# kkClave.net
KiCad netlist of a schematic drawn in EAGLE
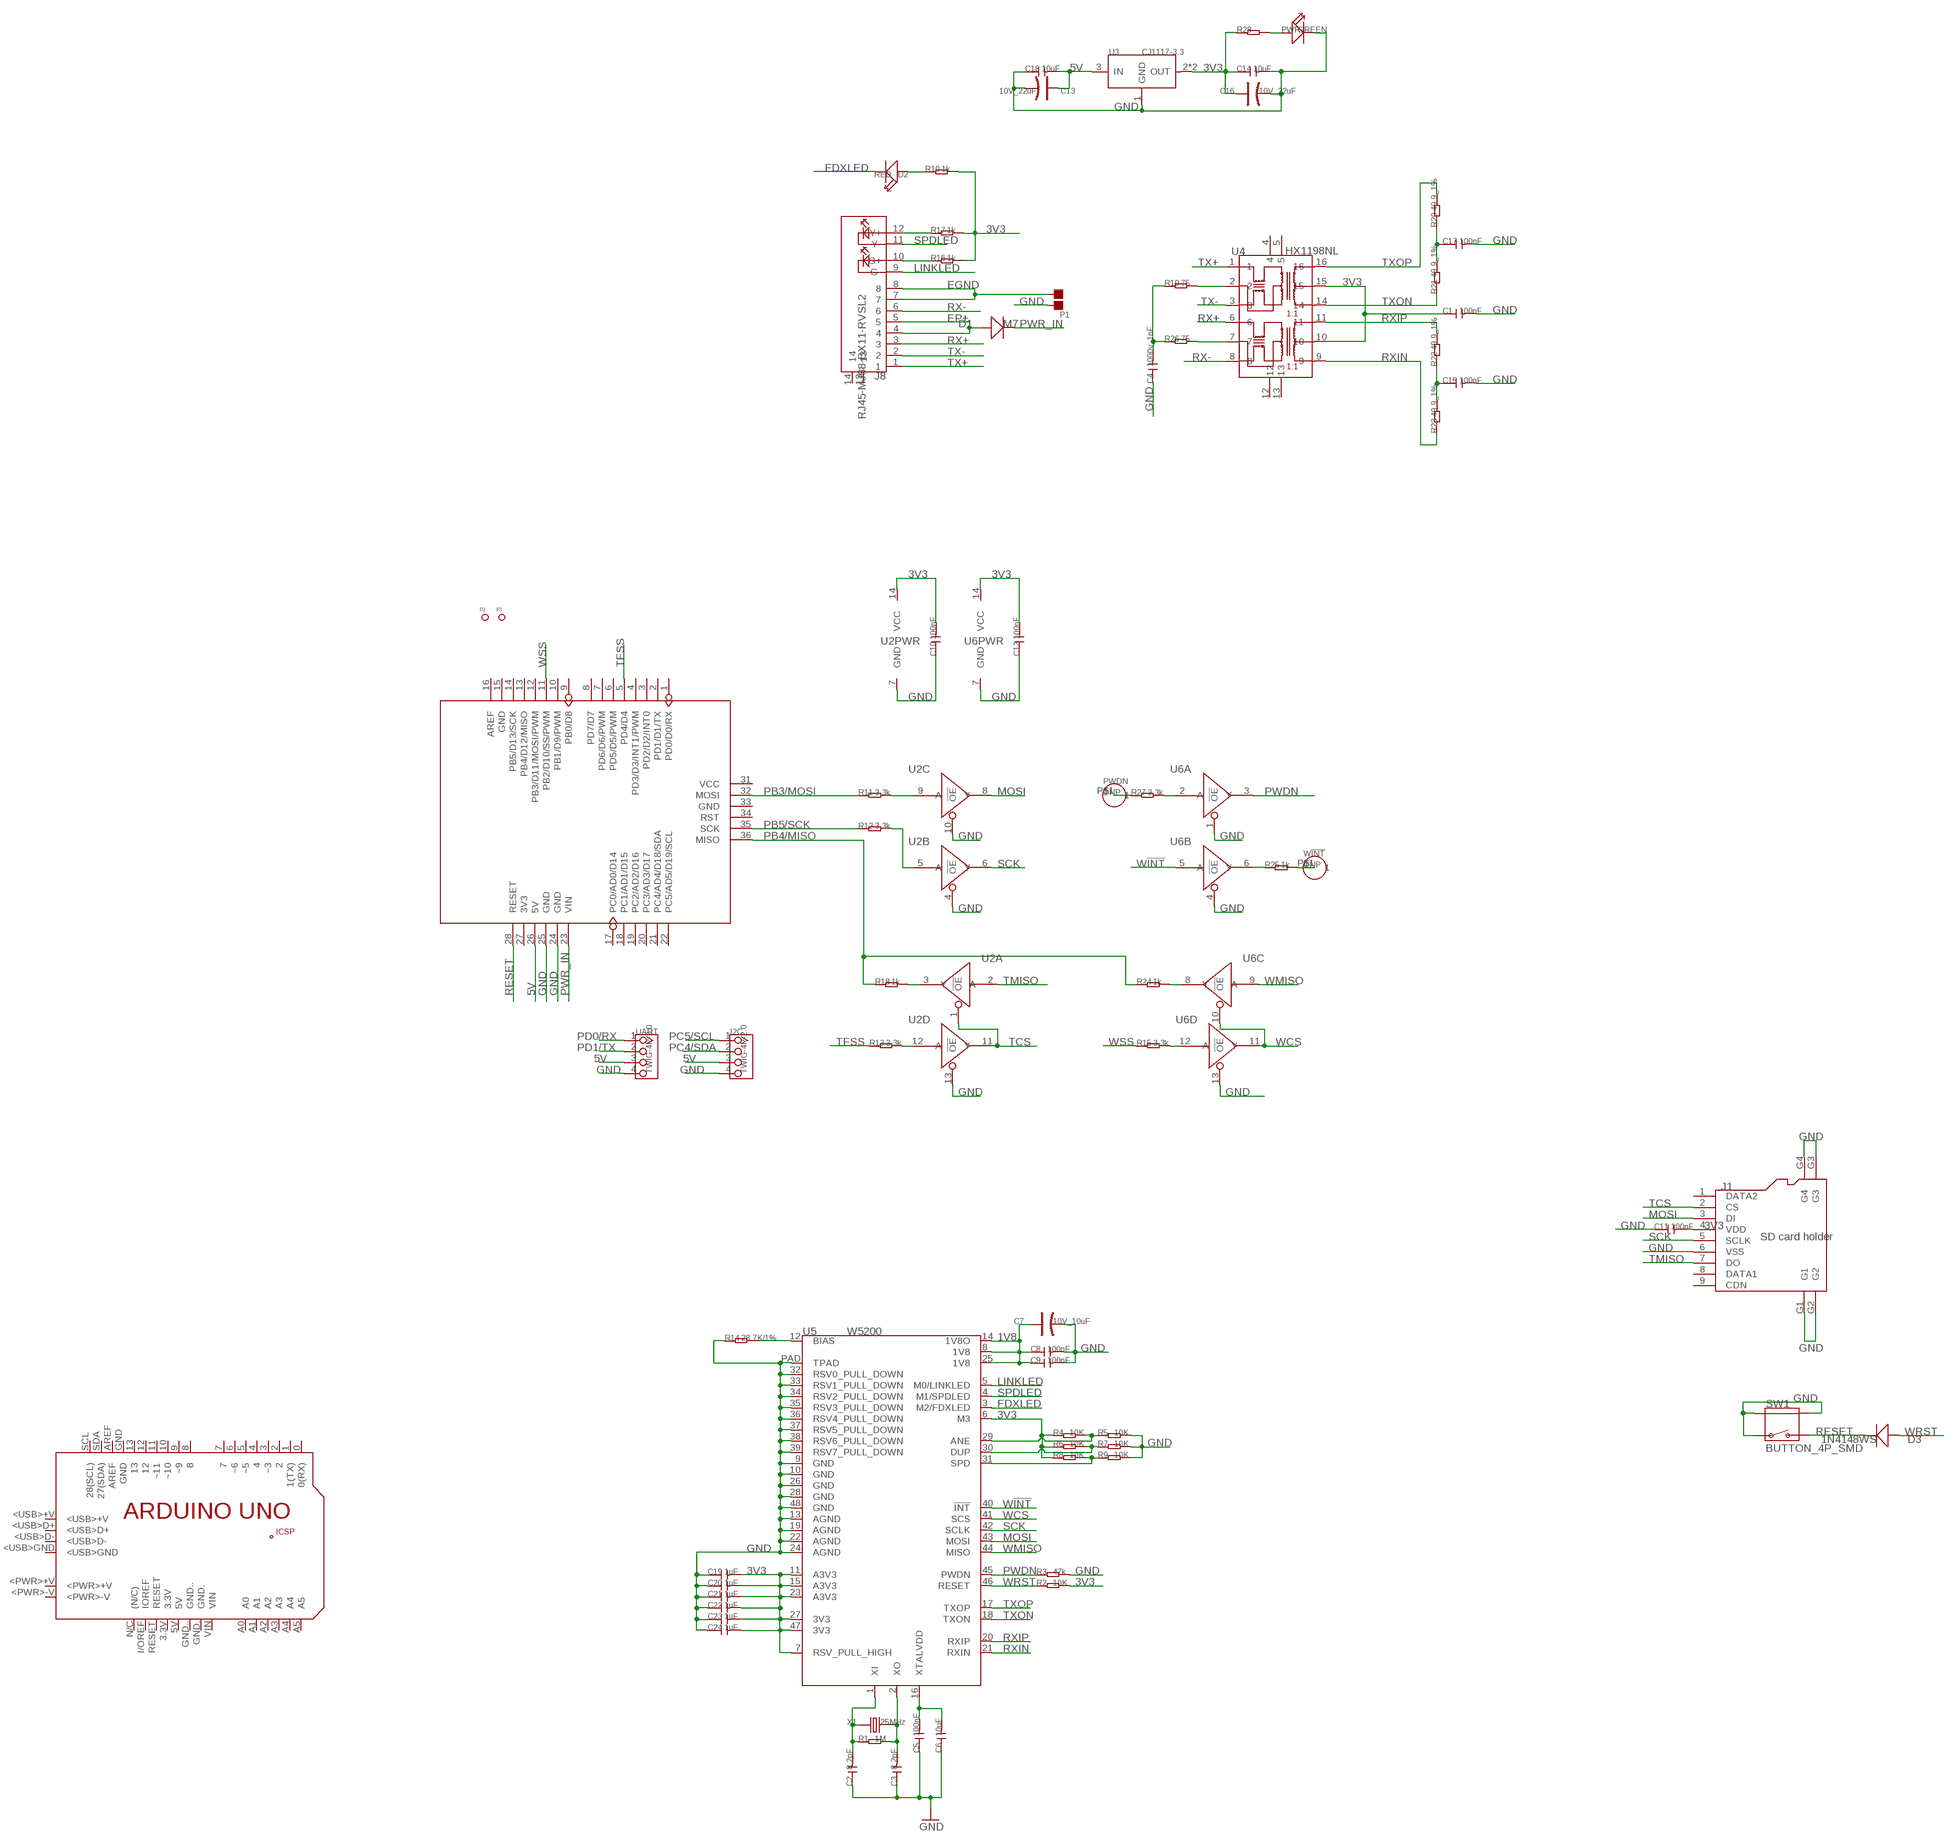
[diagram p0: schematic, sheet 1]

(export (version "E")
  (design (tool "Eeschema 10.0.6"))
  (components
    (comp (ref "C1")
      (value "100nF")
      (footprint "eagle-import:C0603")
      (libsource (lib "eagle-import") (part "C-0603"))
    )
    (comp (ref "C2")
      (value "8.2pF")
      (footprint "eagle-import:C0603")
      (libsource (lib "eagle-import") (part "C-0603"))
    )
    (comp (ref "C3")
      (value "8.2pF")
      (footprint "eagle-import:C0603")
      (libsource (lib "eagle-import") (part "C-0603"))
    )
    (comp (ref "C4")
      (value "1000v_1nF")
      (footprint "eagle-import:C1206")
      (libsource (lib "eagle-import") (part "C-1206"))
    )
    (comp (ref "C5")
      (value "100nF")
      (footprint "eagle-import:C0603")
      (libsource (lib "eagle-import") (part "C-0603"))
    )
    (comp (ref "C6")
      (value "10uF")
      (footprint "eagle-import:C0805")
      (libsource (lib "eagle-import") (part "C-0805"))
    )
    (comp (ref "C7")
      (value "10V_10uF")
      (footprint "eagle-import:AVX-A")
      (libsource (lib "eagle-import") (part "CAP-AVX-A"))
    )
    (comp (ref "C8")
      (value "100nF")
      (footprint "eagle-import:C0603")
      (libsource (lib "eagle-import") (part "C-0603"))
    )
    (comp (ref "C9")
      (value "100nF")
      (footprint "eagle-import:C0603")
      (libsource (lib "eagle-import") (part "C-0603"))
    )
    (comp (ref "C10")
      (value "100nF")
      (footprint "eagle-import:C0603")
      (libsource (lib "eagle-import") (part "C-0603"))
    )
    (comp (ref "C11")
      (value "100nF")
      (footprint "eagle-import:C0603")
      (libsource (lib "eagle-import") (part "C-0603"))
    )
    (comp (ref "C12")
      (value "100nF")
      (footprint "eagle-import:C0603")
      (libsource (lib "eagle-import") (part "C-0603"))
    )
    (comp (ref "C13")
      (value "10V_22uF")
      (footprint "eagle-import:AVX-B")
      (libsource (lib "eagle-import") (part "CAP-AVX-B"))
    )
    (comp (ref "C14")
      (value "10uF")
      (footprint "eagle-import:C0805")
      (libsource (lib "eagle-import") (part "C-0805"))
    )
    (comp (ref "C15")
      (value "100nF")
      (footprint "eagle-import:C0603")
      (libsource (lib "eagle-import") (part "C-0603"))
    )
    (comp (ref "C16")
      (value "10V_22uF")
      (footprint "eagle-import:AVX-B")
      (libsource (lib "eagle-import") (part "CAP-AVX-B"))
    )
    (comp (ref "C17")
      (value "100nF")
      (footprint "eagle-import:C0603")
      (libsource (lib "eagle-import") (part "C-0603"))
    )
    (comp (ref "C18")
      (value "10uF")
      (footprint "eagle-import:C0805")
      (libsource (lib "eagle-import") (part "C-0805"))
    )
    (comp (ref "C19")
      (value "1uF")
      (footprint "eagle-import:C0805")
      (libsource (lib "eagle-import") (part "C-0805"))
    )
    (comp (ref "C20")
      (value "1uF")
      (footprint "eagle-import:C0805")
      (libsource (lib "eagle-import") (part "C-0805"))
    )
    (comp (ref "C21")
      (value "1uF")
      (footprint "eagle-import:C0805")
      (libsource (lib "eagle-import") (part "C-0805"))
    )
    (comp (ref "C22")
      (value "1uF")
      (footprint "eagle-import:C0805")
      (libsource (lib "eagle-import") (part "C-0805"))
    )
    (comp (ref "C23")
      (value "1uF")
      (footprint "eagle-import:C0805")
      (libsource (lib "eagle-import") (part "C-0805"))
    )
    (comp (ref "C24")
      (value "1uF")
      (footprint "eagle-import:C0805")
      (libsource (lib "eagle-import") (part "C-0805"))
    )
    (comp (ref "D1")
      (value "M7")
      (footprint "eagle-import:D2010")
      (libsource (lib "eagle-import") (part "D'SMA'"))
    )
    (comp (ref "D2")
      (value "RED")
      (footprint "eagle-import:LED-0603")
      (libsource (lib "eagle-import") (part "LED'0603'"))
    )
    (comp (ref "D3")
      (value "1N4148WS")
      (footprint "eagle-import:SOD323")
      (libsource (lib "eagle-import") (part "D'0805'"))
    )
    (comp (ref "I2C")
      (value "TWIG-4P-2.0")
      (footprint "eagle-import:4P-2.0")
      (libsource (lib "eagle-import") (part "TWIG-4P-2.0-2.0"))
    )
    (comp (ref "J1")
      (value "SD card holder")
      (footprint "eagle-import:9P-SMD-W_-RING")
      (libsource (lib "eagle-import") (part "HOLDER-MICROSD-9P"))
    )
    (comp (ref "J8")
      (value "RJ45-MJ88-BX11-RVSL2")
      (footprint "eagle-import:RJ45-MJ88-BX11-RVSL2")
      (libsource (lib "eagle-import") (part "RJ45-MJ88-BX11-RVSL2"))
    )
    (comp (ref "P1")
      (value "DNP")
      (footprint "eagle-import:2P-SMD-1.78X1.27")
      (libsource (lib "eagle-import") (part "PAD-JUMPER-2P"))
    )
    (comp (ref "P2")
      (value "PAD-MARK")
      (footprint "eagle-import:ROUND-MARK-1.0")
      (fields (field (name "PARTNO") "DNP"))
      (libsource (lib "eagle-import") (part "PAD-MARK"))
    )
    (comp (ref "P3")
      (value "PAD-MARK")
      (footprint "eagle-import:ROUND-MARK-1.0")
      (fields (field (name "PARTNO") "DNP"))
      (libsource (lib "eagle-import") (part "PAD-MARK"))
    )
    (comp (ref "PCB1")
      (value "ARDUINO_UNO")
      (footprint "eagle-import:ARDUINO_UNO")
      (libsource (lib "eagle-import") (part "ARDUINO_UNO"))
    )
    (comp (ref "PWDN")
      (value "DNP")
      (footprint "eagle-import:1P-65_35MIL")
      (libsource (lib "eagle-import") (part "HEADER-1P-35"))
    )
    (comp (ref "PWR")
      (value "GREEN")
      (footprint "eagle-import:LED-0603")
      (libsource (lib "eagle-import") (part "LED'0603'"))
    )
    (comp (ref "R1")
      (value "1M")
      (footprint "eagle-import:R0603")
      (libsource (lib "eagle-import") (part "R-0603"))
    )
    (comp (ref "R2")
      (value "10K")
      (footprint "eagle-import:R0603")
      (libsource (lib "eagle-import") (part "R-0603"))
    )
    (comp (ref "R3")
      (value "47k")
      (footprint "eagle-import:R0603")
      (libsource (lib "eagle-import") (part "R-0603"))
    )
    (comp (ref "R4")
      (value "10K")
      (footprint "eagle-import:R0603")
      (libsource (lib "eagle-import") (part "R-0603"))
    )
    (comp (ref "R5")
      (value "10K")
      (footprint "eagle-import:R0603")
      (libsource (lib "eagle-import") (part "R-0603"))
    )
    (comp (ref "R6")
      (value "10K")
      (footprint "eagle-import:R0603")
      (libsource (lib "eagle-import") (part "R-0603"))
    )
    (comp (ref "R7")
      (value "10K")
      (footprint "eagle-import:R0603")
      (libsource (lib "eagle-import") (part "R-0603"))
    )
    (comp (ref "R8")
      (value "10K")
      (footprint "eagle-import:R0603")
      (libsource (lib "eagle-import") (part "R-0603"))
    )
    (comp (ref "R9")
      (value "10K")
      (footprint "eagle-import:R0603")
      (libsource (lib "eagle-import") (part "R-0603"))
    )
    (comp (ref "R10")
      (value "1k")
      (footprint "eagle-import:R0603")
      (libsource (lib "eagle-import") (part "R-0603"))
    )
    (comp (ref "R11")
      (value "3.3k")
      (footprint "eagle-import:R0603")
      (libsource (lib "eagle-import") (part "R-0603"))
    )
    (comp (ref "R12")
      (value "3.3k")
      (footprint "eagle-import:R0603")
      (libsource (lib "eagle-import") (part "R-0603"))
    )
    (comp (ref "R13")
      (value "3.3k")
      (footprint "eagle-import:R0603")
      (libsource (lib "eagle-import") (part "R-0603"))
    )
    (comp (ref "R14")
      (value "28.7K/1%")
      (footprint "eagle-import:R0603")
      (libsource (lib "eagle-import") (part "R-0603"))
    )
    (comp (ref "R15")
      (value "3.3k")
      (footprint "eagle-import:R0603")
      (libsource (lib "eagle-import") (part "R-0603"))
    )
    (comp (ref "R16")
      (value "1k")
      (footprint "eagle-import:R0603")
      (libsource (lib "eagle-import") (part "R-0603"))
    )
    (comp (ref "R17")
      (value "1k")
      (footprint "eagle-import:R0603")
      (libsource (lib "eagle-import") (part "R-0603"))
    )
    (comp (ref "R18")
      (value "1k")
      (footprint "eagle-import:R0603")
      (libsource (lib "eagle-import") (part "R-0603"))
    )
    (comp (ref "R19")
      (value "75")
      (footprint "eagle-import:R0603")
      (libsource (lib "eagle-import") (part "R-0603"))
    )
    (comp (ref "R20")
      (value "49.9_1%")
      (footprint "eagle-import:R0603")
      (libsource (lib "eagle-import") (part "R-0603"))
    )
    (comp (ref "R21")
      (value "49.9_1%")
      (footprint "eagle-import:R0603")
      (libsource (lib "eagle-import") (part "R-0603"))
    )
    (comp (ref "R22")
      (value "49.9_1%")
      (footprint "eagle-import:R0603")
      (libsource (lib "eagle-import") (part "R-0603"))
    )
    (comp (ref "R23")
      (value "49.9_1%")
      (footprint "eagle-import:R0603")
      (libsource (lib "eagle-import") (part "R-0603"))
    )
    (comp (ref "R24")
      (value "1k")
      (footprint "eagle-import:R0603")
      (libsource (lib "eagle-import") (part "R-0603"))
    )
    (comp (ref "R25")
      (value "1k")
      (footprint "eagle-import:R0603")
      (libsource (lib "eagle-import") (part "R-0603"))
    )
    (comp (ref "R26")
      (value "75")
      (footprint "eagle-import:R0603")
      (libsource (lib "eagle-import") (part "R-0603"))
    )
    (comp (ref "R27")
      (value "3.3k")
      (footprint "eagle-import:R0603")
      (libsource (lib "eagle-import") (part "R-0603"))
    )
    (comp (ref "R28")
      (value "R-0603")
      (footprint "eagle-import:R0603")
      (libsource (lib "eagle-import") (part "R-0603"))
    )
    (comp (ref "SW1")
      (value "BUTTON_4P_SMD")
      (footprint "eagle-import:4P-SMD-7X3.5X3.5")
      (libsource (lib "eagle-import") (part "BUTTON_4P_SMD"))
    )
    (comp (ref "U1")
      (value "ARDUINO")
      (footprint "eagle-import:ARDUINO")
      (libsource (lib "eagle-import") (part "ARDUINO"))
    )
    (comp (ref "U2")
      (value "74VHC125PW")
      (footprint "eagle-import:TSSOP14")
      (libsource (lib "eagle-import") (part "74V125PWHC"))
    )
    (comp (ref "U3")
      (value "CJ1117-3.3")
      (footprint "eagle-import:SOT-223")
      (libsource (lib "eagle-import") (part "LD1117S"))
    )
    (comp (ref "U4")
      (value "HX1198NL")
      (footprint "eagle-import:SOIC16-9.53")
      (libsource (lib "eagle-import") (part "HX1198NL"))
    )
    (comp (ref "U5")
      (value "W5200")
      (footprint "eagle-import:QFN48")
      (libsource (lib "eagle-import") (part "W5200"))
    )
    (comp (ref "U6")
      (value "74VHC125PW")
      (footprint "eagle-import:TSSOP14")
      (libsource (lib "eagle-import") (part "74V125PWHC"))
    )
    (comp (ref "UART")
      (value "TWIG-4P-2.0")
      (footprint "eagle-import:4P-2.0")
      (libsource (lib "eagle-import") (part "TWIG-4P-2.0-2.0"))
    )
    (comp (ref "W!INT")
      (value "DNP")
      (footprint "eagle-import:1P-65_35MIL")
      (libsource (lib "eagle-import") (part "HEADER-1P-35"))
    )
    (comp (ref "X1")
      (value "25MHz")
      (footprint "eagle-import:2P-SMD-5X3.2")
      (libsource (lib "eagle-import") (part "CRYSTAL'5032'"))
    )
  )
  (nets
    (net (code "1") (name "/1V8") (class "Default")
      (node (ref "C7") (pin "+") (pinfunction "+_+") (pintype "passive"))
      (node (ref "C8") (pin "1") (pinfunction "1_1") (pintype "passive"))
      (node (ref "C9") (pin "1") (pinfunction "1_1") (pintype "passive"))
      (node (ref "U5") (pin "14") (pinfunction "1V8O_14") (pintype "bidirectional"))
      (node (ref "U5") (pin "25") (pinfunction "1V8_25") (pintype "bidirectional"))
      (node (ref "U5") (pin "8") (pinfunction "1V8_8") (pintype "bidirectional"))
    )
    (net (code "2") (name "/3V3") (class "Default")
      (node (ref "C1") (pin "1") (pinfunction "1_1") (pintype "passive"))
      (node (ref "C10") (pin "2") (pinfunction "2_2") (pintype "passive"))
      (node (ref "C11") (pin "2") (pinfunction "2_2") (pintype "passive"))
      (node (ref "C12") (pin "2") (pinfunction "2_2") (pintype "passive"))
      (node (ref "C14") (pin "1") (pinfunction "1_1") (pintype "passive"))
      (node (ref "C16") (pin "+") (pinfunction "+_+") (pintype "passive"))
      (node (ref "C19") (pin "2") (pinfunction "2_2") (pintype "passive"))
      (node (ref "C20") (pin "2") (pinfunction "2_2") (pintype "passive"))
      (node (ref "C21") (pin "2") (pinfunction "2_2") (pintype "passive"))
      (node (ref "C22") (pin "2") (pinfunction "2_2") (pintype "passive"))
      (node (ref "C23") (pin "2") (pinfunction "2_2") (pintype "passive"))
      (node (ref "C24") (pin "2") (pinfunction "2_2") (pintype "passive"))
      (node (ref "J1") (pin "4") (pinfunction "VDD_4") (pintype "bidirectional"))
      (node (ref "R10") (pin "2") (pinfunction "2_2") (pintype "passive"))
      (node (ref "R16") (pin "2") (pinfunction "2_2") (pintype "passive"))
      (node (ref "R17") (pin "2") (pinfunction "2_2") (pintype "passive"))
      (node (ref "R2") (pin "2") (pinfunction "2_2") (pintype "passive"))
      (node (ref "R28") (pin "1") (pinfunction "1_1") (pintype "passive"))
      (node (ref "R4") (pin "1") (pinfunction "1_1") (pintype "passive"))
      (node (ref "R6") (pin "1") (pinfunction "1_1") (pintype "passive"))
      (node (ref "R8") (pin "1") (pinfunction "1_1") (pintype "passive"))
      (node (ref "U2") (pin "14") (pinfunction "VCC_14") (pintype "power_in"))
      (node (ref "U3") (pin "2") (pinfunction "OUT_2") (pintype "bidirectional"))
      (node (ref "U3") (pin "TER") (pinfunction "OUT_TER") (pintype "bidirectional"))
      (node (ref "U4") (pin "10") (pinfunction "10_10") (pintype "bidirectional"))
      (node (ref "U4") (pin "15") (pinfunction "15_15") (pintype "bidirectional"))
      (node (ref "U5") (pin "11") (pinfunction "A3V3_11") (pintype "bidirectional"))
      (node (ref "U5") (pin "15") (pinfunction "A3V3_15") (pintype "bidirectional"))
      (node (ref "U5") (pin "23") (pinfunction "A3V3_23") (pintype "bidirectional"))
      (node (ref "U5") (pin "27") (pinfunction "3V3_27") (pintype "bidirectional"))
      (node (ref "U5") (pin "47") (pinfunction "3V3_47") (pintype "bidirectional"))
      (node (ref "U5") (pin "6") (pinfunction "M3_6") (pintype "bidirectional"))
      (node (ref "U5") (pin "7") (pinfunction "RSV_PULL_HIGH_7") (pintype "bidirectional"))
      (node (ref "U6") (pin "14") (pinfunction "VCC_14") (pintype "power_in"))
    )
    (net (code "3") (name "/5V") (class "Default")
      (node (ref "C13") (pin "+") (pinfunction "+_+") (pintype "passive"))
      (node (ref "C18") (pin "2") (pinfunction "2_2") (pintype "passive"))
      (node (ref "I2C") (pin "3") (pinfunction "3_3") (pintype "bidirectional"))
      (node (ref "U1") (pin "26") (pinfunction "5V_26") (pintype "bidirectional"))
      (node (ref "U3") (pin "3") (pinfunction "IN_3") (pintype "bidirectional"))
      (node (ref "UART") (pin "3") (pinfunction "3_3") (pintype "bidirectional"))
    )
    (net (code "4") (name "/EGND") (class "Default")
      (node (ref "J8") (pin "7") (pinfunction "7_7") (pintype "bidirectional"))
      (node (ref "J8") (pin "8") (pinfunction "8_8") (pintype "bidirectional"))
      (node (ref "P1") (pin "1") (pinfunction "1_1") (pintype "bidirectional"))
    )
    (net (code "5") (name "/EP+") (class "Default")
      (node (ref "D1") (pin "+") (pinfunction "+_+") (pintype "passive"))
      (node (ref "J8") (pin "4") (pinfunction "4_4") (pintype "bidirectional"))
      (node (ref "J8") (pin "5") (pinfunction "5_5") (pintype "bidirectional"))
    )
    (net (code "6") (name "/FDXLED") (class "Default")
      (node (ref "D2") (pin "-") (pinfunction "-_-") (pintype "passive"))
      (node (ref "U5") (pin "3") (pinfunction "M2/FDXLED_3") (pintype "bidirectional"))
    )
    (net (code "7") (name "/LINKLED") (class "Default")
      (node (ref "J8") (pin "9") (pinfunction "G-_9") (pintype "bidirectional"))
      (node (ref "U5") (pin "5") (pinfunction "M0/LINKLED_5") (pintype "bidirectional"))
    )
    (net (code "8") (name "/MOSI") (class "Default")
      (node (ref "J1") (pin "3") (pinfunction "DI_3") (pintype "bidirectional"))
      (node (ref "U2") (pin "8") (pinfunction "Y_8") (pintype "bidirectional"))
      (node (ref "U5") (pin "43") (pinfunction "MOSI_43") (pintype "bidirectional"))
    )
    (net (code "9") (name "/PB3{slash}MOSI") (class "Default")
      (node (ref "R11") (pin "1") (pinfunction "1_1") (pintype "passive"))
      (node (ref "U1") (pin "32") (pinfunction "MOSI_32") (pintype "bidirectional"))
    )
    (net (code "10") (name "/PB4{slash}MISO") (class "Default")
      (node (ref "R18") (pin "1") (pinfunction "1_1") (pintype "passive"))
      (node (ref "R24") (pin "1") (pinfunction "1_1") (pintype "passive"))
      (node (ref "U1") (pin "36") (pinfunction "MISO_36") (pintype "bidirectional"))
    )
    (net (code "11") (name "/PB5{slash}SCK") (class "Default")
      (node (ref "R12") (pin "1") (pinfunction "1_1") (pintype "passive"))
      (node (ref "U1") (pin "35") (pinfunction "SCK_35") (pintype "bidirectional"))
    )
    (net (code "12") (name "/PC4{slash}SDA") (class "Default")
      (node (ref "I2C") (pin "2") (pinfunction "2_2") (pintype "bidirectional"))
    )
    (net (code "13") (name "/PC5{slash}SCL") (class "Default")
      (node (ref "I2C") (pin "1") (pinfunction "1_1") (pintype "bidirectional"))
    )
    (net (code "14") (name "/PD0{slash}RX") (class "Default")
      (node (ref "UART") (pin "1") (pinfunction "1_1") (pintype "bidirectional"))
    )
    (net (code "15") (name "/PD1{slash}TX") (class "Default")
      (node (ref "UART") (pin "2") (pinfunction "2_2") (pintype "bidirectional"))
    )
    (net (code "16") (name "/PWDN") (class "Default")
      (node (ref "R3") (pin "1") (pinfunction "1_1") (pintype "passive"))
      (node (ref "U5") (pin "45") (pinfunction "PWDN_45") (pintype "bidirectional"))
      (node (ref "U6") (pin "3") (pinfunction "Y_3") (pintype "bidirectional"))
    )
    (net (code "17") (name "/PWR_IN") (class "Default")
      (node (ref "D1") (pin "-") (pinfunction "-_-") (pintype "passive"))
      (node (ref "U1") (pin "23") (pinfunction "VIN_23") (pintype "bidirectional"))
    )
    (net (code "18") (name "/RESET") (class "Default")
      (node (ref "D3") (pin "-") (pinfunction "-_-") (pintype "passive"))
      (node (ref "SW1") (pin "2") (pinfunction "2_2") (pintype "bidirectional"))
      (node (ref "U1") (pin "28") (pinfunction "RESET_28") (pintype "bidirectional"))
    )
    (net (code "19") (name "/RX+") (class "Default")
      (node (ref "J8") (pin "3") (pinfunction "3_3") (pintype "bidirectional"))
      (node (ref "U4") (pin "6") (pinfunction "6_6") (pintype "bidirectional"))
    )
    (net (code "20") (name "/RX-") (class "Default")
      (node (ref "J8") (pin "6") (pinfunction "6_6") (pintype "bidirectional"))
      (node (ref "U4") (pin "8") (pinfunction "8_8") (pintype "bidirectional"))
    )
    (net (code "21") (name "/RXIN") (class "Default")
      (node (ref "R23") (pin "1") (pinfunction "1_1") (pintype "passive"))
      (node (ref "U4") (pin "9") (pinfunction "9_9") (pintype "bidirectional"))
      (node (ref "U5") (pin "21") (pinfunction "RXIN_21") (pintype "bidirectional"))
    )
    (net (code "22") (name "/RXIP") (class "Default")
      (node (ref "R22") (pin "2") (pinfunction "2_2") (pintype "passive"))
      (node (ref "U4") (pin "11") (pinfunction "11_11") (pintype "bidirectional"))
      (node (ref "U5") (pin "20") (pinfunction "RXIP_20") (pintype "bidirectional"))
    )
    (net (code "23") (name "/SCK") (class "Default")
      (node (ref "J1") (pin "5") (pinfunction "SCLK_5") (pintype "bidirectional"))
      (node (ref "U2") (pin "6") (pinfunction "Y_6") (pintype "bidirectional"))
      (node (ref "U5") (pin "42") (pinfunction "SCLK_42") (pintype "bidirectional"))
    )
    (net (code "24") (name "/SPDLED") (class "Default")
      (node (ref "J8") (pin "11") (pinfunction "Y-_11") (pintype "bidirectional"))
      (node (ref "U5") (pin "4") (pinfunction "M1/SPDLED_4") (pintype "bidirectional"))
    )
    (net (code "25") (name "/TCS") (class "Default")
      (node (ref "J1") (pin "2") (pinfunction "CS_2") (pintype "bidirectional"))
      (node (ref "U2") (pin "1") (pinfunction "~{OE}_1") (pintype "bidirectional"))
      (node (ref "U2") (pin "11") (pinfunction "Y_11") (pintype "bidirectional"))
    )
    (net (code "26") (name "/TFSS") (class "Default")
      (node (ref "R13") (pin "1") (pinfunction "1_1") (pintype "passive"))
      (node (ref "U1") (pin "5") (pinfunction "PD4/D4_5") (pintype "bidirectional"))
    )
    (net (code "27") (name "/TMISO") (class "Default")
      (node (ref "J1") (pin "7") (pinfunction "DO_7") (pintype "bidirectional"))
      (node (ref "U2") (pin "2") (pinfunction "A_2") (pintype "bidirectional"))
    )
    (net (code "28") (name "/TX+") (class "Default")
      (node (ref "J8") (pin "1") (pinfunction "1_1") (pintype "bidirectional"))
      (node (ref "U4") (pin "1") (pinfunction "1_1") (pintype "bidirectional"))
    )
    (net (code "29") (name "/TX-") (class "Default")
      (node (ref "J8") (pin "2") (pinfunction "2_2") (pintype "bidirectional"))
      (node (ref "U4") (pin "3") (pinfunction "3_3") (pintype "bidirectional"))
    )
    (net (code "30") (name "/TXON") (class "Default")
      (node (ref "R21") (pin "1") (pinfunction "1_1") (pintype "passive"))
      (node (ref "U4") (pin "14") (pinfunction "14_14") (pintype "bidirectional"))
      (node (ref "U5") (pin "18") (pinfunction "TXON_18") (pintype "bidirectional"))
    )
    (net (code "31") (name "/TXOP") (class "Default")
      (node (ref "R20") (pin "2") (pinfunction "2_2") (pintype "passive"))
      (node (ref "U4") (pin "16") (pinfunction "16_16") (pintype "bidirectional"))
      (node (ref "U5") (pin "17") (pinfunction "TXOP_17") (pintype "bidirectional"))
    )
    (net (code "32") (name "/WCS") (class "Default")
      (node (ref "U5") (pin "41") (pinfunction "SCS_41") (pintype "bidirectional"))
      (node (ref "U6") (pin "10") (pinfunction "~{OE}_10") (pintype "bidirectional"))
      (node (ref "U6") (pin "11") (pinfunction "Y_11") (pintype "bidirectional"))
    )
    (net (code "33") (name "/WMISO") (class "Default")
      (node (ref "U5") (pin "44") (pinfunction "MISO_44") (pintype "bidirectional"))
      (node (ref "U6") (pin "9") (pinfunction "A_9") (pintype "bidirectional"))
    )
    (net (code "34") (name "/WRST") (class "Default")
      (node (ref "D3") (pin "+") (pinfunction "+_+") (pintype "passive"))
      (node (ref "R2") (pin "1") (pinfunction "1_1") (pintype "passive"))
      (node (ref "U5") (pin "46") (pinfunction "RESET_46") (pintype "bidirectional"))
    )
    (net (code "35") (name "/WSS") (class "Default")
      (node (ref "R15") (pin "1") (pinfunction "1_1") (pintype "passive"))
      (node (ref "U1") (pin "11") (pinfunction "PB2/D10/SS/PWM_11") (pintype "bidirectional"))
    )
    (net (code "36") (name "/W~{INT}") (class "Default")
      (node (ref "U5") (pin "40") (pinfunction "~{INT}_40") (pintype "bidirectional"))
      (node (ref "U6") (pin "5") (pinfunction "A_5") (pintype "bidirectional"))
    )
    (net (code "37") (name "GND") (class "Default")
      (node (ref "C1") (pin "2") (pinfunction "2_2") (pintype "passive"))
      (node (ref "C10") (pin "1") (pinfunction "1_1") (pintype "passive"))
      (node (ref "C11") (pin "1") (pinfunction "1_1") (pintype "passive"))
      (node (ref "C12") (pin "1") (pinfunction "1_1") (pintype "passive"))
      (node (ref "C13") (pin "-") (pinfunction "-_-") (pintype "passive"))
      (node (ref "C14") (pin "2") (pinfunction "2_2") (pintype "passive"))
      (node (ref "C15") (pin "2") (pinfunction "2_2") (pintype "passive"))
      (node (ref "C16") (pin "-") (pinfunction "-_-") (pintype "passive"))
      (node (ref "C17") (pin "2") (pinfunction "2_2") (pintype "passive"))
      (node (ref "C18") (pin "1") (pinfunction "1_1") (pintype "passive"))
      (node (ref "C19") (pin "1") (pinfunction "1_1") (pintype "passive"))
      (node (ref "C2") (pin "1") (pinfunction "1_1") (pintype "passive"))
      (node (ref "C20") (pin "1") (pinfunction "1_1") (pintype "passive"))
      (node (ref "C21") (pin "1") (pinfunction "1_1") (pintype "passive"))
      (node (ref "C22") (pin "1") (pinfunction "1_1") (pintype "passive"))
      (node (ref "C23") (pin "1") (pinfunction "1_1") (pintype "passive"))
      (node (ref "C24") (pin "1") (pinfunction "1_1") (pintype "passive"))
      (node (ref "C3") (pin "1") (pinfunction "1_1") (pintype "passive"))
      (node (ref "C4") (pin "1") (pinfunction "1_1") (pintype "passive"))
      (node (ref "C5") (pin "1") (pinfunction "1_1") (pintype "passive"))
      (node (ref "C6") (pin "1") (pinfunction "1_1") (pintype "passive"))
      (node (ref "C7") (pin "-") (pinfunction "-_-") (pintype "passive"))
      (node (ref "C8") (pin "2") (pinfunction "2_2") (pintype "passive"))
      (node (ref "C9") (pin "2") (pinfunction "2_2") (pintype "passive"))
      (node (ref "I2C") (pin "4") (pinfunction "4_4") (pintype "bidirectional"))
      (node (ref "J1") (pin "6") (pinfunction "VSS_6") (pintype "bidirectional"))
      (node (ref "J1") (pin "G1") (pinfunction "G1_G1") (pintype "bidirectional"))
      (node (ref "J1") (pin "G2") (pinfunction "G2_G2") (pintype "bidirectional"))
      (node (ref "J1") (pin "G3") (pinfunction "G3_G3") (pintype "bidirectional"))
      (node (ref "J1") (pin "G4") (pinfunction "G4_G4") (pintype "bidirectional"))
      (node (ref "P1") (pin "2") (pinfunction "2_2") (pintype "bidirectional"))
      (node (ref "PWR") (pin "-") (pinfunction "-_-") (pintype "passive"))
      (node (ref "R14") (pin "1") (pinfunction "1_1") (pintype "passive"))
      (node (ref "R3") (pin "2") (pinfunction "2_2") (pintype "passive"))
      (node (ref "R5") (pin "2") (pinfunction "2_2") (pintype "passive"))
      (node (ref "R7") (pin "2") (pinfunction "2_2") (pintype "passive"))
      (node (ref "R9") (pin "2") (pinfunction "2_2") (pintype "passive"))
      (node (ref "SW1") (pin "1") (pinfunction "1_1") (pintype "bidirectional"))
      (node (ref "SW1") (pin "S1") (pinfunction "S1_S1") (pintype "bidirectional"))
      (node (ref "SW1") (pin "S2") (pinfunction "S2_S2") (pintype "bidirectional"))
      (node (ref "U1") (pin "24") (pinfunction "GND_24") (pintype "bidirectional"))
      (node (ref "U1") (pin "25") (pinfunction "GND_25") (pintype "bidirectional"))
      (node (ref "U2") (pin "10") (pinfunction "~{OE}_10") (pintype "bidirectional"))
      (node (ref "U2") (pin "13") (pinfunction "~{OE}_13") (pintype "bidirectional"))
      (node (ref "U2") (pin "4") (pinfunction "~{OE}_4") (pintype "bidirectional"))
      (node (ref "U2") (pin "7") (pinfunction "GND_7") (pintype "power_in"))
      (node (ref "U3") (pin "1") (pinfunction "GND_1") (pintype "bidirectional"))
      (node (ref "U5") (pin "10") (pinfunction "GND_10") (pintype "bidirectional"))
      (node (ref "U5") (pin "13") (pinfunction "AGND_13") (pintype "bidirectional"))
      (node (ref "U5") (pin "19") (pinfunction "AGND_19") (pintype "bidirectional"))
      (node (ref "U5") (pin "22") (pinfunction "AGND_22") (pintype "bidirectional"))
      (node (ref "U5") (pin "24") (pinfunction "AGND_24") (pintype "bidirectional"))
      (node (ref "U5") (pin "26") (pinfunction "GND_26") (pintype "bidirectional"))
      (node (ref "U5") (pin "28") (pinfunction "GND_28") (pintype "bidirectional"))
      (node (ref "U5") (pin "32") (pinfunction "RSV0_PULL_DOWN_32") (pintype "bidirectional"))
      (node (ref "U5") (pin "33") (pinfunction "RSV1_PULL_DOWN_33") (pintype "bidirectional"))
      (node (ref "U5") (pin "34") (pinfunction "RSV2_PULL_DOWN_34") (pintype "bidirectional"))
      (node (ref "U5") (pin "35") (pinfunction "RSV3_PULL_DOWN_35") (pintype "bidirectional"))
      (node (ref "U5") (pin "36") (pinfunction "RSV4_PULL_DOWN_36") (pintype "bidirectional"))
      (node (ref "U5") (pin "37") (pinfunction "RSV5_PULL_DOWN_37") (pintype "bidirectional"))
      (node (ref "U5") (pin "38") (pinfunction "RSV6_PULL_DOWN_38") (pintype "bidirectional"))
      (node (ref "U5") (pin "39") (pinfunction "RSV7_PULL_DOWN_39") (pintype "bidirectional"))
      (node (ref "U5") (pin "48") (pinfunction "GND_48") (pintype "bidirectional"))
      (node (ref "U5") (pin "9") (pinfunction "GND_9") (pintype "bidirectional"))
      (node (ref "U5") (pin "PAD") (pinfunction "TPAD_PAD") (pintype "bidirectional"))
      (node (ref "U6") (pin "1") (pinfunction "~{OE}_1") (pintype "bidirectional"))
      (node (ref "U6") (pin "13") (pinfunction "~{OE}_13") (pintype "bidirectional"))
      (node (ref "U6") (pin "4") (pinfunction "~{OE}_4") (pintype "bidirectional"))
      (node (ref "U6") (pin "7") (pinfunction "GND_7") (pintype "power_in"))
      (node (ref "UART") (pin "4") (pinfunction "4_4") (pintype "bidirectional"))
    )
    (net (code "38") (name "Net-(C4-Pad2)") (class "Default")
      (node (ref "C4") (pin "2") (pinfunction "2_2") (pintype "passive"))
      (node (ref "R19") (pin "1") (pinfunction "1_1") (pintype "passive"))
      (node (ref "R26") (pin "1") (pinfunction "1_1") (pintype "passive"))
    )
    (net (code "39") (name "Net-(C15-Pad1)") (class "Default")
      (node (ref "C15") (pin "1") (pinfunction "1_1") (pintype "passive"))
      (node (ref "R22") (pin "1") (pinfunction "1_1") (pintype "passive"))
      (node (ref "R23") (pin "2") (pinfunction "2_2") (pintype "passive"))
    )
    (net (code "40") (name "Net-(C17-Pad1)") (class "Default")
      (node (ref "C17") (pin "1") (pinfunction "1_1") (pintype "passive"))
      (node (ref "R20") (pin "1") (pinfunction "1_1") (pintype "passive"))
      (node (ref "R21") (pin "2") (pinfunction "2_2") (pintype "passive"))
    )
    (net (code "41") (name "Net-(D2-Pad+)") (class "Default")
      (node (ref "D2") (pin "+") (pinfunction "+_+") (pintype "passive"))
      (node (ref "R10") (pin "1") (pinfunction "1_1") (pintype "passive"))
    )
    (net (code "42") (name "Net-(J8-G+)") (class "Default")
      (node (ref "J8") (pin "10") (pinfunction "G+_10") (pintype "bidirectional"))
      (node (ref "R16") (pin "1") (pinfunction "1_1") (pintype "passive"))
    )
    (net (code "43") (name "Net-(J8-Y+)") (class "Default")
      (node (ref "J8") (pin "12") (pinfunction "Y+_12") (pintype "bidirectional"))
      (node (ref "R17") (pin "1") (pinfunction "1_1") (pintype "passive"))
    )
    (net (code "44") (name "Net-(PWDN-1)") (class "Default")
      (node (ref "PWDN") (pin "P$1") (pinfunction "1_P$1") (pintype "bidirectional"))
      (node (ref "R27") (pin "1") (pinfunction "1_1") (pintype "passive"))
    )
    (net (code "45") (name "Net-(PWR-Pad+)") (class "Default")
      (node (ref "PWR") (pin "+") (pinfunction "+_+") (pintype "passive"))
      (node (ref "R28") (pin "2") (pinfunction "2_2") (pintype "passive"))
    )
    (net (code "46") (name "Net-(R19-Pad2)") (class "Default")
      (node (ref "R19") (pin "2") (pinfunction "2_2") (pintype "passive"))
      (node (ref "U4") (pin "2") (pinfunction "2_2") (pintype "bidirectional"))
    )
    (net (code "47") (name "Net-(R26-Pad2)") (class "Default")
      (node (ref "R26") (pin "2") (pinfunction "2_2") (pintype "passive"))
      (node (ref "U4") (pin "7") (pinfunction "7_7") (pintype "bidirectional"))
    )
    (net (code "48") (name "Net-(U2A-Y)") (class "Default")
      (node (ref "R18") (pin "2") (pinfunction "2_2") (pintype "passive"))
      (node (ref "U2") (pin "3") (pinfunction "Y_3") (pintype "bidirectional"))
    )
    (net (code "49") (name "Net-(U2B-A)") (class "Default")
      (node (ref "R12") (pin "2") (pinfunction "2_2") (pintype "passive"))
      (node (ref "U2") (pin "5") (pinfunction "A_5") (pintype "bidirectional"))
    )
    (net (code "50") (name "Net-(U2C-A)") (class "Default")
      (node (ref "R11") (pin "2") (pinfunction "2_2") (pintype "passive"))
      (node (ref "U2") (pin "9") (pinfunction "A_9") (pintype "bidirectional"))
    )
    (net (code "51") (name "Net-(U2D-A)") (class "Default")
      (node (ref "R13") (pin "2") (pinfunction "2_2") (pintype "passive"))
      (node (ref "U2") (pin "12") (pinfunction "A_12") (pintype "bidirectional"))
    )
    (net (code "52") (name "Net-(U5-ANE)") (class "Default")
      (node (ref "R4") (pin "2") (pinfunction "2_2") (pintype "passive"))
      (node (ref "R5") (pin "1") (pinfunction "1_1") (pintype "passive"))
      (node (ref "U5") (pin "29") (pinfunction "ANE_29") (pintype "bidirectional"))
    )
    (net (code "53") (name "Net-(U5-BIAS)") (class "Default")
      (node (ref "R14") (pin "2") (pinfunction "2_2") (pintype "passive"))
      (node (ref "U5") (pin "12") (pinfunction "BIAS_12") (pintype "bidirectional"))
    )
    (net (code "54") (name "Net-(U5-DUP)") (class "Default")
      (node (ref "R6") (pin "2") (pinfunction "2_2") (pintype "passive"))
      (node (ref "R7") (pin "1") (pinfunction "1_1") (pintype "passive"))
      (node (ref "U5") (pin "30") (pinfunction "DUP_30") (pintype "bidirectional"))
    )
    (net (code "55") (name "Net-(U5-SPD)") (class "Default")
      (node (ref "R8") (pin "2") (pinfunction "2_2") (pintype "passive"))
      (node (ref "R9") (pin "1") (pinfunction "1_1") (pintype "passive"))
      (node (ref "U5") (pin "31") (pinfunction "SPD_31") (pintype "bidirectional"))
    )
    (net (code "56") (name "Net-(U5-XI)") (class "Default")
      (node (ref "C2") (pin "2") (pinfunction "2_2") (pintype "passive"))
      (node (ref "R1") (pin "1") (pinfunction "1_1") (pintype "passive"))
      (node (ref "U5") (pin "1") (pinfunction "XI_1") (pintype "bidirectional"))
      (node (ref "X1") (pin "1") (pinfunction "1_1") (pintype "passive"))
    )
    (net (code "57") (name "Net-(U5-XO)") (class "Default")
      (node (ref "C3") (pin "2") (pinfunction "2_2") (pintype "passive"))
      (node (ref "R1") (pin "2") (pinfunction "2_2") (pintype "passive"))
      (node (ref "U5") (pin "2") (pinfunction "XO_2") (pintype "bidirectional"))
      (node (ref "X1") (pin "2") (pinfunction "2_2") (pintype "passive"))
    )
    (net (code "58") (name "Net-(U5-XTALVDD)") (class "Default")
      (node (ref "C5") (pin "2") (pinfunction "2_2") (pintype "passive"))
      (node (ref "C6") (pin "2") (pinfunction "2_2") (pintype "passive"))
      (node (ref "U5") (pin "16") (pinfunction "XTALVDD_16") (pintype "bidirectional"))
    )
    (net (code "59") (name "Net-(U6A-A)") (class "Default")
      (node (ref "R27") (pin "2") (pinfunction "2_2") (pintype "passive"))
      (node (ref "U6") (pin "2") (pinfunction "A_2") (pintype "bidirectional"))
    )
    (net (code "60") (name "Net-(U6B-Y)") (class "Default")
      (node (ref "R25") (pin "1") (pinfunction "1_1") (pintype "passive"))
      (node (ref "U6") (pin "6") (pinfunction "Y_6") (pintype "bidirectional"))
    )
    (net (code "61") (name "Net-(U6C-Y)") (class "Default")
      (node (ref "R24") (pin "2") (pinfunction "2_2") (pintype "passive"))
      (node (ref "U6") (pin "8") (pinfunction "Y_8") (pintype "bidirectional"))
    )
    (net (code "62") (name "Net-(U6D-A)") (class "Default")
      (node (ref "R15") (pin "2") (pinfunction "2_2") (pintype "passive"))
      (node (ref "U6") (pin "12") (pinfunction "A_12") (pintype "bidirectional"))
    )
    (net (code "63") (name "Net-(W!INT-1)") (class "Default")
      (node (ref "R25") (pin "2") (pinfunction "2_2") (pintype "passive"))
      (node (ref "W!INT") (pin "P$1") (pinfunction "1_P$1") (pintype "bidirectional"))
    )
    (net (code "64") (name "unconnected-(J1-CDN-Pad9)") (class "Default")
      (node (ref "J1") (pin "9") (pinfunction "CDN_9") (pintype "bidirectional"))
    )
    (net (code "65") (name "unconnected-(J1-DATA1-Pad8)") (class "Default")
      (node (ref "J1") (pin "8") (pinfunction "DATA1_8") (pintype "bidirectional"))
    )
    (net (code "66") (name "unconnected-(J1-DATA2-Pad1)") (class "Default")
      (node (ref "J1") (pin "1") (pinfunction "DATA2_1") (pintype "bidirectional"))
    )
    (net (code "67") (name "unconnected-(J8-Pad13)") (class "Default")
      (node (ref "J8") (pin "13") (pinfunction "13_13") (pintype "bidirectional"))
    )
    (net (code "68") (name "unconnected-(J8-Pad14)") (class "Default")
      (node (ref "J8") (pin "14") (pinfunction "14_14") (pintype "bidirectional"))
    )
    (net (code "69") (name "unconnected-(PCB1-(N{slash}C)-PadN{slash}C)") (class "Default")
      (node (ref "PCB1") (pin "N/C") (pinfunction "(N/C)_N/C") (pintype "bidirectional"))
    )
    (net (code "70") (name "unconnected-(PCB1-0(RX)-Pad0)") (class "Default")
      (node (ref "PCB1") (pin "0") (pinfunction "0(RX)_0") (pintype "bidirectional"))
    )
    (net (code "71") (name "unconnected-(PCB1-1(TX)-Pad1)") (class "Default")
      (node (ref "PCB1") (pin "1") (pinfunction "1(TX)_1") (pintype "bidirectional"))
    )
    (net (code "72") (name "unconnected-(PCB1-27(SDA)-PadSDA)") (class "Default")
      (node (ref "PCB1") (pin "SDA") (pinfunction "27(SDA)_SDA") (pintype "bidirectional"))
    )
    (net (code "73") (name "unconnected-(PCB1-28(SCL)-PadSCL)") (class "Default")
      (node (ref "PCB1") (pin "SCL") (pinfunction "28(SCL)_SCL") (pintype "bidirectional"))
    )
    (net (code "74") (name "unconnected-(PCB1-IOREF-PadI{slash}OREF)") (class "Default")
      (node (ref "PCB1") (pin "I/OREF") (pinfunction "IOREF_I/OREF") (pintype "bidirectional"))
    )
    (net (code "75") (name "unconnected-(PCB1-Pad+5V)") (class "Default")
      (node (ref "PCB1") (pin "+5V") (pinfunction "+5V_+5V") (pintype "bidirectional"))
    )
    (net (code "76") (name "unconnected-(PCB1-Pad2)") (class "Default")
      (node (ref "PCB1") (pin "2") (pinfunction "2_2") (pintype "bidirectional"))
    )
    (net (code "77") (name "unconnected-(PCB1-Pad3.3V)") (class "Default")
      (node (ref "PCB1") (pin "3.3V") (pinfunction "3.3V_3.3V") (pintype "bidirectional"))
    )
    (net (code "78") (name "unconnected-(PCB1-Pad4)") (class "Default")
      (node (ref "PCB1") (pin "4") (pinfunction "4_4") (pintype "bidirectional"))
    )
    (net (code "79") (name "unconnected-(PCB1-Pad5V)") (class "Default")
      (node (ref "PCB1") (pin "5V") (pinfunction "5V_5V") (pintype "bidirectional"))
    )
    (net (code "80") (name "unconnected-(PCB1-Pad7)") (class "Default")
      (node (ref "PCB1") (pin "7") (pinfunction "7_7") (pintype "bidirectional"))
    )
    (net (code "81") (name "unconnected-(PCB1-Pad8)") (class "Default")
      (node (ref "PCB1") (pin "8") (pinfunction "8_8") (pintype "bidirectional"))
    )
    (net (code "82") (name "unconnected-(PCB1-Pad12)") (class "Default")
      (node (ref "PCB1") (pin "12") (pinfunction "12_12") (pintype "bidirectional"))
    )
    (net (code "83") (name "unconnected-(PCB1-Pad13)") (class "Default")
      (node (ref "PCB1") (pin "13") (pinfunction "13_13") (pintype "bidirectional"))
    )
    (net (code "84") (name "unconnected-(PCB1-Pad<PWR>+V)") (class "Default")
      (node (ref "PCB1") (pin "<PWR>+V") (pinfunction "<PWR>+V_<PWR>+V") (pintype "bidirectional"))
    )
    (net (code "85") (name "unconnected-(PCB1-Pad<PWR>-V)") (class "Default")
      (node (ref "PCB1") (pin "<PWR>-V") (pinfunction "<PWR>-V_<PWR>-V") (pintype "bidirectional"))
    )
    (net (code "86") (name "unconnected-(PCB1-Pad<USB>+V)") (class "Default")
      (node (ref "PCB1") (pin "<USB>+V") (pinfunction "<USB>+V_<USB>+V") (pintype "bidirectional"))
    )
    (net (code "87") (name "unconnected-(PCB1-Pad<USB>D+)") (class "Default")
      (node (ref "PCB1") (pin "<USB>D+") (pinfunction "<USB>D+_<USB>D+") (pintype "bidirectional"))
    )
    (net (code "88") (name "unconnected-(PCB1-Pad<USB>D-)") (class "Default")
      (node (ref "PCB1") (pin "<USB>D-") (pinfunction "<USB>D-_<USB>D-") (pintype "bidirectional"))
    )
    (net (code "89") (name "unconnected-(PCB1-Pad<USB>GND)") (class "Default")
      (node (ref "PCB1") (pin "<USB>GND") (pinfunction "<USB>GND_<USB>GND") (pintype "bidirectional"))
    )
    (net (code "90") (name "unconnected-(PCB1-PadA0)") (class "Default")
      (node (ref "PCB1") (pin "A0") (pinfunction "A0_A0") (pintype "bidirectional"))
    )
    (net (code "91") (name "unconnected-(PCB1-PadA1)") (class "Default")
      (node (ref "PCB1") (pin "A1") (pinfunction "A1_A1") (pintype "bidirectional"))
    )
    (net (code "92") (name "unconnected-(PCB1-PadA2)") (class "Default")
      (node (ref "PCB1") (pin "A2") (pinfunction "A2_A2") (pintype "bidirectional"))
    )
    (net (code "93") (name "unconnected-(PCB1-PadA3)") (class "Default")
      (node (ref "PCB1") (pin "A3") (pinfunction "A3_A3") (pintype "bidirectional"))
    )
    (net (code "94") (name "unconnected-(PCB1-PadA4)") (class "Default")
      (node (ref "PCB1") (pin "A4") (pinfunction "A4_A4") (pintype "bidirectional"))
    )
    (net (code "95") (name "unconnected-(PCB1-PadA5)") (class "Default")
      (node (ref "PCB1") (pin "A5") (pinfunction "A5_A5") (pintype "bidirectional"))
    )
    (net (code "96") (name "unconnected-(PCB1-PadAREF)") (class "Default")
      (node (ref "PCB1") (pin "AREF") (pinfunction "AREF_AREF") (pintype "bidirectional"))
    )
    (net (code "97") (name "unconnected-(PCB1-PadGND)") (class "Default")
      (node (ref "PCB1") (pin "GND") (pinfunction "GND_GND") (pintype "bidirectional"))
    )
    (net (code "98") (name "unconnected-(PCB1-PadGND.)") (class "Default")
      (node (ref "PCB1") (pin "GND.") (pinfunction "GND._GND.") (pintype "bidirectional"))
    )
    (net (code "99") (name "unconnected-(PCB1-PadGND..)") (class "Default")
      (node (ref "PCB1") (pin "GND..") (pinfunction "GND.._GND..") (pintype "bidirectional"))
    )
    (net (code "100") (name "unconnected-(PCB1-PadGND_)") (class "Default")
      (node (ref "PCB1") (pin "GND_") (pinfunction "GND__GND_") (pintype "bidirectional"))
    )
    (net (code "101") (name "unconnected-(PCB1-PadMISO)") (class "Default")
      (node (ref "PCB1") (pin "MISO") (pinfunction "MISO_MISO") (pintype "bidirectional"))
    )
    (net (code "102") (name "unconnected-(PCB1-PadMOSI)") (class "Default")
      (node (ref "PCB1") (pin "MOSI") (pinfunction "MOSI_MOSI") (pintype "bidirectional"))
    )
    (net (code "103") (name "unconnected-(PCB1-PadRESET)") (class "Default")
      (node (ref "PCB1") (pin "RESET") (pinfunction "RESET_RESET") (pintype "bidirectional"))
    )
    (net (code "104") (name "unconnected-(PCB1-PadRESET.)") (class "Default")
      (node (ref "PCB1") (pin "RESET.") (pinfunction "RESET._RESET.") (pintype "bidirectional"))
    )
    (net (code "105") (name "unconnected-(PCB1-PadSCK)") (class "Default")
      (node (ref "PCB1") (pin "SCK") (pinfunction "SCK_SCK") (pintype "bidirectional"))
    )
    (net (code "106") (name "unconnected-(PCB1-PadVIN)") (class "Default")
      (node (ref "PCB1") (pin "VIN") (pinfunction "VIN_VIN") (pintype "bidirectional"))
    )
    (net (code "107") (name "unconnected-(PCB1-~{3}-Pad3)") (class "Default")
      (node (ref "PCB1") (pin "3") (pinfunction "~{3}_3") (pintype "bidirectional"))
    )
    (net (code "108") (name "unconnected-(PCB1-~{5}-Pad5)") (class "Default")
      (node (ref "PCB1") (pin "5") (pinfunction "~{5}_5") (pintype "bidirectional"))
    )
    (net (code "109") (name "unconnected-(PCB1-~{6}-Pad6)") (class "Default")
      (node (ref "PCB1") (pin "6") (pinfunction "~{6}_6") (pintype "bidirectional"))
    )
    (net (code "110") (name "unconnected-(PCB1-~{9}-Pad9)") (class "Default")
      (node (ref "PCB1") (pin "9") (pinfunction "~{9}_9") (pintype "bidirectional"))
    )
    (net (code "111") (name "unconnected-(PCB1-~{10}-Pad10)") (class "Default")
      (node (ref "PCB1") (pin "10") (pinfunction "~{10}_10") (pintype "bidirectional"))
    )
    (net (code "112") (name "unconnected-(PCB1-~{11}-Pad11)") (class "Default")
      (node (ref "PCB1") (pin "11") (pinfunction "~{11}_11") (pintype "bidirectional"))
    )
    (net (code "113") (name "unconnected-(U1-3V3-Pad27)") (class "Default")
      (node (ref "U1") (pin "27") (pinfunction "3V3_27") (pintype "bidirectional"))
    )
    (net (code "114") (name "unconnected-(U1-AREF-Pad16)") (class "Default")
      (node (ref "U1") (pin "16") (pinfunction "AREF_16") (pintype "bidirectional"))
    )
    (net (code "115") (name "unconnected-(U1-GND-Pad15)") (class "Default")
      (node (ref "U1") (pin "15") (pinfunction "GND_15") (pintype "bidirectional"))
    )
    (net (code "116") (name "unconnected-(U1-GND-Pad33)") (class "Default")
      (node (ref "U1") (pin "33") (pinfunction "GND_33") (pintype "bidirectional"))
    )
    (net (code "117") (name "unconnected-(U1-PB0{slash}D8-Pad9)") (class "Default")
      (node (ref "U1") (pin "9") (pinfunction "PB0/D8_9") (pintype "bidirectional"))
    )
    (net (code "118") (name "unconnected-(U1-PB1{slash}D9{slash}PWM-Pad10)") (class "Default")
      (node (ref "U1") (pin "10") (pinfunction "PB1/D9/PWM_10") (pintype "bidirectional"))
    )
    (net (code "119") (name "unconnected-(U1-PB3{slash}D11{slash}MOSI{slash}PWM-Pad12)") (class "Default")
      (node (ref "U1") (pin "12") (pinfunction "PB3/D11/MOSI/PWM_12") (pintype "bidirectional"))
    )
    (net (code "120") (name "unconnected-(U1-PB4{slash}D12{slash}MISO-Pad13)") (class "Default")
      (node (ref "U1") (pin "13") (pinfunction "PB4/D12/MISO_13") (pintype "bidirectional"))
    )
    (net (code "121") (name "unconnected-(U1-PB5{slash}D13{slash}SCK-Pad14)") (class "Default")
      (node (ref "U1") (pin "14") (pinfunction "PB5/D13/SCK_14") (pintype "bidirectional"))
    )
    (net (code "122") (name "unconnected-(U1-PC0{slash}AD0{slash}D14-Pad17)") (class "Default")
      (node (ref "U1") (pin "17") (pinfunction "PC0/AD0/D14_17") (pintype "bidirectional"))
    )
    (net (code "123") (name "unconnected-(U1-PC1{slash}AD1{slash}D15-Pad18)") (class "Default")
      (node (ref "U1") (pin "18") (pinfunction "PC1/AD1/D15_18") (pintype "bidirectional"))
    )
    (net (code "124") (name "unconnected-(U1-PC2{slash}AD2{slash}D16-Pad19)") (class "Default")
      (node (ref "U1") (pin "19") (pinfunction "PC2/AD2/D16_19") (pintype "bidirectional"))
    )
    (net (code "125") (name "unconnected-(U1-PC3{slash}AD3{slash}D17-Pad20)") (class "Default")
      (node (ref "U1") (pin "20") (pinfunction "PC3/AD3/D17_20") (pintype "bidirectional"))
    )
    (net (code "126") (name "unconnected-(U1-PC4{slash}AD4{slash}D18{slash}SDA-Pad21)") (class "Default")
      (node (ref "U1") (pin "21") (pinfunction "PC4/AD4/D18/SDA_21") (pintype "bidirectional"))
    )
    (net (code "127") (name "unconnected-(U1-PC5{slash}AD5{slash}D19{slash}SCL-Pad22)") (class "Default")
      (node (ref "U1") (pin "22") (pinfunction "PC5/AD5/D19/SCL_22") (pintype "bidirectional"))
    )
    (net (code "128") (name "unconnected-(U1-PD0{slash}D0{slash}RX-Pad1)") (class "Default")
      (node (ref "U1") (pin "1") (pinfunction "PD0/D0/RX_1") (pintype "bidirectional"))
    )
    (net (code "129") (name "unconnected-(U1-PD1{slash}D1{slash}TX-Pad2)") (class "Default")
      (node (ref "U1") (pin "2") (pinfunction "PD1/D1/TX_2") (pintype "bidirectional"))
    )
    (net (code "130") (name "unconnected-(U1-PD2{slash}D2{slash}INT0-Pad3)") (class "Default")
      (node (ref "U1") (pin "3") (pinfunction "PD2/D2/INT0_3") (pintype "bidirectional"))
    )
    (net (code "131") (name "unconnected-(U1-PD3{slash}D3{slash}INT1{slash}PWM-Pad4)") (class "Default")
      (node (ref "U1") (pin "4") (pinfunction "PD3/D3/INT1/PWM_4") (pintype "bidirectional"))
    )
    (net (code "132") (name "unconnected-(U1-PD5{slash}D5{slash}PWM-Pad6)") (class "Default")
      (node (ref "U1") (pin "6") (pinfunction "PD5/D5/PWM_6") (pintype "bidirectional"))
    )
    (net (code "133") (name "unconnected-(U1-PD6{slash}D6{slash}PWM-Pad7)") (class "Default")
      (node (ref "U1") (pin "7") (pinfunction "PD6/D6/PWM_7") (pintype "bidirectional"))
    )
    (net (code "134") (name "unconnected-(U1-PD7{slash}D7-Pad8)") (class "Default")
      (node (ref "U1") (pin "8") (pinfunction "PD7/D7_8") (pintype "bidirectional"))
    )
    (net (code "135") (name "unconnected-(U1-RST-Pad34)") (class "Default")
      (node (ref "U1") (pin "34") (pinfunction "RST_34") (pintype "bidirectional"))
    )
    (net (code "136") (name "unconnected-(U1-VCC-Pad31)") (class "Default")
      (node (ref "U1") (pin "31") (pinfunction "VCC_31") (pintype "bidirectional"))
    )
    (net (code "137") (name "unconnected-(U4-Pad4)") (class "Default")
      (node (ref "U4") (pin "4") (pinfunction "4_4") (pintype "bidirectional"))
    )
    (net (code "138") (name "unconnected-(U4-Pad5)") (class "Default")
      (node (ref "U4") (pin "5") (pinfunction "5_5") (pintype "bidirectional"))
    )
    (net (code "139") (name "unconnected-(U4-Pad12)") (class "Default")
      (node (ref "U4") (pin "12") (pinfunction "12_12") (pintype "bidirectional"))
    )
    (net (code "140") (name "unconnected-(U4-Pad13)") (class "Default")
      (node (ref "U4") (pin "13") (pinfunction "13_13") (pintype "bidirectional"))
    )
  )
)
